# Telliskivi2014MainBoard.net
KiCad netlist of a schematic drawn in Altium Designer
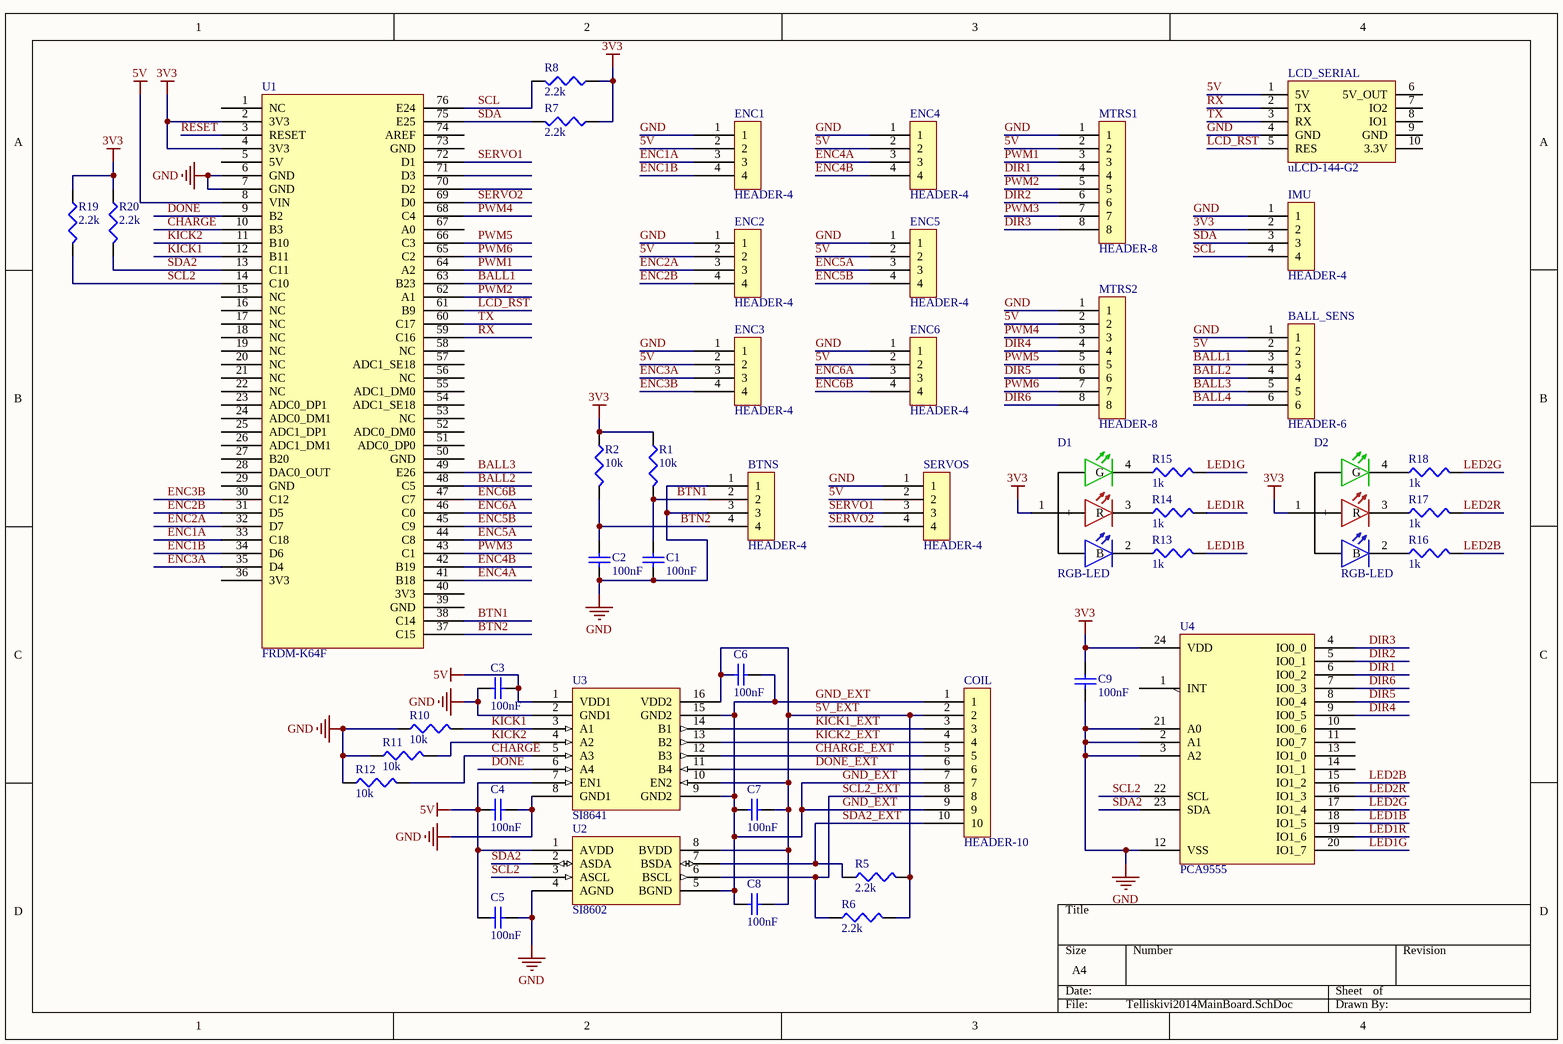
[diagram p0: Telliskivi2014MainBoard.SchDoc]

(export (version "E")
  (design (tool "Eeschema 10.0.6"))
  (components
    (comp (ref "BALL_SENS")
      (value "HEADER-6")
      (footprint "MICRO-MATCH-6")
      (libsource (lib "connectors") (part "HEADER-6"))
    )
    (comp (ref "BTNS")
      (value "HEADER-4")
      (footprint "MICRO-MATCH-4")
      (libsource (lib "connectors") (part "HEADER-4"))
    )
    (comp (ref "C1")
      (value "100nF")
      (footprint "1608[0603]")
      (description "Capacitor (Semiconductor SIM Model)")
      (fields (field (name "PUBLISHER") "Altium Limited"))
      (libsource (lib "Miscellaneous Devices") (part "Cap Semi"))
    )
    (comp (ref "C2")
      (value "100nF")
      (footprint "1608[0603]")
      (description "Capacitor (Semiconductor SIM Model)")
      (fields (field (name "PUBLISHER") "Altium Limited"))
      (libsource (lib "Miscellaneous Devices") (part "Cap Semi"))
    )
    (comp (ref "C3")
      (value "100nF")
      (footprint "1608[0603]")
      (description "Capacitor (Semiconductor SIM Model)")
      (fields (field (name "PUBLISHER") "Altium Limited"))
      (libsource (lib "Miscellaneous Devices") (part "Cap Semi"))
    )
    (comp (ref "C4")
      (value "100nF")
      (footprint "1608[0603]")
      (description "Capacitor (Semiconductor SIM Model)")
      (fields (field (name "PUBLISHER") "Altium Limited"))
      (libsource (lib "Miscellaneous Devices") (part "Cap Semi"))
    )
    (comp (ref "C5")
      (value "100nF")
      (footprint "1608[0603]")
      (description "Capacitor (Semiconductor SIM Model)")
      (fields (field (name "PUBLISHER") "Altium Limited"))
      (libsource (lib "Miscellaneous Devices") (part "Cap Semi"))
    )
    (comp (ref "C6")
      (value "100nF")
      (footprint "1608[0603]")
      (description "Capacitor (Semiconductor SIM Model)")
      (fields (field (name "PUBLISHER") "Altium Limited"))
      (libsource (lib "Miscellaneous Devices") (part "Cap Semi"))
    )
    (comp (ref "C7")
      (value "100nF")
      (footprint "1608[0603]")
      (description "Capacitor (Semiconductor SIM Model)")
      (fields (field (name "PUBLISHER") "Altium Limited"))
      (libsource (lib "Miscellaneous Devices") (part "Cap Semi"))
    )
    (comp (ref "C8")
      (value "100nF")
      (footprint "1608[0603]")
      (description "Capacitor (Semiconductor SIM Model)")
      (fields (field (name "PUBLISHER") "Altium Limited"))
      (libsource (lib "Miscellaneous Devices") (part "Cap Semi"))
    )
    (comp (ref "C9")
      (value "100nF")
      (footprint "1608[0603]")
      (description "Capacitor (Semiconductor SIM Model)")
      (fields (field (name "PUBLISHER") "Altium Limited"))
      (libsource (lib "Miscellaneous Devices") (part "Cap Semi"))
    )
    (comp (ref "COIL")
      (value "HEADER-10")
      (footprint "MICRO-MATCH-10")
      (libsource (lib "connectors") (part "HEADER-10"))
    )
    (comp (ref "D1") (value "RGB-LED") (footprint "RGB-LED") (libsource (lib "misc") (part "RGB-LED")))
    (comp (ref "D2") (value "RGB-LED") (footprint "RGB-LED") (libsource (lib "misc") (part "RGB-LED")))
    (comp (ref "ENC1")
      (value "HEADER-4")
      (footprint "MICRO-MATCH-4")
      (libsource (lib "connectors") (part "HEADER-4"))
    )
    (comp (ref "ENC2")
      (value "HEADER-4")
      (footprint "MICRO-MATCH-4")
      (libsource (lib "connectors") (part "HEADER-4"))
    )
    (comp (ref "ENC3")
      (value "HEADER-4")
      (footprint "MICRO-MATCH-4")
      (libsource (lib "connectors") (part "HEADER-4"))
    )
    (comp (ref "ENC4")
      (value "HEADER-4")
      (footprint "MICRO-MATCH-4")
      (libsource (lib "connectors") (part "HEADER-4"))
    )
    (comp (ref "ENC5")
      (value "HEADER-4")
      (footprint "MICRO-MATCH-4")
      (libsource (lib "connectors") (part "HEADER-4"))
    )
    (comp (ref "ENC6")
      (value "HEADER-4")
      (footprint "MICRO-MATCH-4")
      (libsource (lib "connectors") (part "HEADER-4"))
    )
    (comp (ref "IMU")
      (value "HEADER-4")
      (footprint "MICRO-MATCH-4")
      (libsource (lib "connectors") (part "HEADER-4"))
    )
    (comp (ref "LCD_SERIAL")
      (value "uLCD-144-G2")
      (footprint "uLCD-144-G2-NO-OVERLAY")
      (libsource (lib "misc") (part "uLCD-144-G2"))
    )
    (comp (ref "MTRS1")
      (value "HEADER-8")
      (footprint "MICRO-MATCH-8")
      (libsource (lib "connectors") (part "HEADER-8"))
    )
    (comp (ref "MTRS2")
      (value "HEADER-8")
      (footprint "MICRO-MATCH-8")
      (libsource (lib "connectors") (part "HEADER-8"))
    )
    (comp (ref "R1")
      (value "10k")
      (footprint "J1-0603")
      (description "Resistor")
      (fields (field (name "PUBLISHER") "Altium Limited"))
      (libsource (lib "Miscellaneous Devices") (part "Res3"))
    )
    (comp (ref "R2")
      (value "10k")
      (footprint "J1-0603")
      (description "Resistor")
      (fields (field (name "PUBLISHER") "Altium Limited"))
      (libsource (lib "Miscellaneous Devices") (part "Res3"))
    )
    (comp (ref "R5")
      (value "2.2k")
      (footprint "J1-0603")
      (description "Resistor")
      (fields (field (name "PUBLISHER") "Altium Limited"))
      (libsource (lib "Miscellaneous Devices") (part "Res3"))
    )
    (comp (ref "R6")
      (value "2.2k")
      (footprint "J1-0603")
      (description "Resistor")
      (fields (field (name "PUBLISHER") "Altium Limited"))
      (libsource (lib "Miscellaneous Devices") (part "Res3"))
    )
    (comp (ref "R7")
      (value "2.2k")
      (footprint "J1-0603")
      (description "Resistor")
      (fields (field (name "PUBLISHER") "Altium Limited"))
      (libsource (lib "Miscellaneous Devices") (part "Res3"))
    )
    (comp (ref "R8")
      (value "2.2k")
      (footprint "J1-0603")
      (description "Resistor")
      (fields (field (name "PUBLISHER") "Altium Limited"))
      (libsource (lib "Miscellaneous Devices") (part "Res3"))
    )
    (comp (ref "R10")
      (value "10k")
      (footprint "J1-0603")
      (description "Resistor")
      (fields (field (name "PUBLISHER") "Altium Limited"))
      (libsource (lib "Miscellaneous Devices") (part "Res3"))
    )
    (comp (ref "R11")
      (value "10k")
      (footprint "J1-0603")
      (description "Resistor")
      (fields (field (name "PUBLISHER") "Altium Limited"))
      (libsource (lib "Miscellaneous Devices") (part "Res3"))
    )
    (comp (ref "R12")
      (value "10k")
      (footprint "J1-0603")
      (description "Resistor")
      (fields (field (name "PUBLISHER") "Altium Limited"))
      (libsource (lib "Miscellaneous Devices") (part "Res3"))
    )
    (comp (ref "R13")
      (value "1k")
      (footprint "J1-0603")
      (description "Resistor")
      (fields (field (name "PUBLISHER") "Altium Limited"))
      (libsource (lib "Miscellaneous Devices") (part "Res3"))
    )
    (comp (ref "R14")
      (value "1k")
      (footprint "J1-0603")
      (description "Resistor")
      (fields (field (name "PUBLISHER") "Altium Limited"))
      (libsource (lib "Miscellaneous Devices") (part "Res3"))
    )
    (comp (ref "R15")
      (value "1k")
      (footprint "J1-0603")
      (description "Resistor")
      (fields (field (name "PUBLISHER") "Altium Limited"))
      (libsource (lib "Miscellaneous Devices") (part "Res3"))
    )
    (comp (ref "R16")
      (value "1k")
      (footprint "J1-0603")
      (description "Resistor")
      (fields (field (name "PUBLISHER") "Altium Limited"))
      (libsource (lib "Miscellaneous Devices") (part "Res3"))
    )
    (comp (ref "R17")
      (value "1k")
      (footprint "J1-0603")
      (description "Resistor")
      (fields (field (name "PUBLISHER") "Altium Limited"))
      (libsource (lib "Miscellaneous Devices") (part "Res3"))
    )
    (comp (ref "R18")
      (value "1k")
      (footprint "J1-0603")
      (description "Resistor")
      (fields (field (name "PUBLISHER") "Altium Limited"))
      (libsource (lib "Miscellaneous Devices") (part "Res3"))
    )
    (comp (ref "R19")
      (value "2.2k")
      (footprint "J1-0603")
      (description "Resistor")
      (fields (field (name "PUBLISHER") "Altium Limited"))
      (libsource (lib "Miscellaneous Devices") (part "Res3"))
    )
    (comp (ref "R20")
      (value "2.2k")
      (footprint "J1-0603")
      (description "Resistor")
      (fields (field (name "PUBLISHER") "Altium Limited"))
      (libsource (lib "Miscellaneous Devices") (part "Res3"))
    )
    (comp (ref "SERVOS")
      (value "HEADER-4")
      (footprint "MICRO-MATCH-4")
      (libsource (lib "connectors") (part "HEADER-4"))
    )
    (comp (ref "U1")
      (value "FRDM-K64F")
      (footprint "FRDM-K64F-SMT-NO-OVERLAY")
      (libsource (lib "mbed") (part "FRDM-K64F"))
    )
    (comp (ref "U2") (value "SI8602") (footprint "SOIC8") (libsource (lib "digital") (part "SI8602")))
    (comp (ref "U3") (value "SI8641") (footprint "SOIC16") (libsource (lib "digital") (part "SI8641")))
    (comp (ref "U4") (value "PCA9555") (footprint "TSSOP24") (libsource (lib "digital") (part "PCA9555")))
  )
  (nets
    (net (code "1") (name "/5V_EXT") (class "Default")
      (node (ref "C6") (pin "1") (pinfunction "1_1") (pintype "passive"))
      (node (ref "C7") (pin "2") (pinfunction "2_2") (pintype "passive"))
      (node (ref "C8") (pin "2") (pinfunction "2_2") (pintype "passive"))
      (node (ref "COIL") (pin "2") (pinfunction "2_2") (pintype "passive"))
      (node (ref "R5") (pin "2") (pinfunction "2_2") (pintype "passive"))
      (node (ref "R6") (pin "2") (pinfunction "2_2") (pintype "passive"))
      (node (ref "U2") (pin "8") (pinfunction "BVDD_8") (pintype "power_in"))
      (node (ref "U3") (pin "10") (pinfunction "EN2_10") (pintype "input"))
      (node (ref "U3") (pin "16") (pinfunction "VDD2_16") (pintype "power_in"))
    )
    (net (code "2") (name "/BALL1") (class "Default")
      (node (ref "BALL_SENS") (pin "3") (pinfunction "3_3") (pintype "passive"))
      (node (ref "U1") (pin "63") (pinfunction "B23_63") (pintype "passive"))
    )
    (net (code "3") (name "/BALL2") (class "Default")
      (node (ref "BALL_SENS") (pin "4") (pinfunction "4_4") (pintype "passive"))
      (node (ref "U1") (pin "48") (pinfunction "C5_48") (pintype "passive"))
    )
    (net (code "4") (name "/BALL3") (class "Default")
      (node (ref "BALL_SENS") (pin "5") (pinfunction "5_5") (pintype "passive"))
      (node (ref "U1") (pin "49") (pinfunction "E26_49") (pintype "passive"))
    )
    (net (code "5") (name "/BALL4") (class "Default")
      (node (ref "BALL_SENS") (pin "6") (pinfunction "6_6") (pintype "passive"))
    )
    (net (code "6") (name "/BTN1") (class "Default")
      (node (ref "BTNS") (pin "2") (pinfunction "2_2") (pintype "passive"))
      (node (ref "C1") (pin "2") (pinfunction "2_2") (pintype "passive"))
      (node (ref "R1") (pin "2") (pinfunction "2_2") (pintype "passive"))
      (node (ref "U1") (pin "38") (pinfunction "C14_38") (pintype "passive"))
    )
    (net (code "7") (name "/BTN2") (class "Default")
      (node (ref "BTNS") (pin "4") (pinfunction "4_4") (pintype "passive"))
      (node (ref "C2") (pin "2") (pinfunction "2_2") (pintype "passive"))
      (node (ref "R2") (pin "2") (pinfunction "2_2") (pintype "passive"))
      (node (ref "U1") (pin "37") (pinfunction "C15_37") (pintype "passive"))
    )
    (net (code "8") (name "/CHARGE") (class "Default")
      (node (ref "R12") (pin "2") (pinfunction "2_2") (pintype "passive"))
      (node (ref "U1") (pin "10") (pinfunction "B3_10") (pintype "passive"))
      (node (ref "U3") (pin "5") (pinfunction "A3_5") (pintype "input"))
    )
    (net (code "9") (name "/CHARGE_EXT") (class "Default")
      (node (ref "COIL") (pin "5") (pinfunction "5_5") (pintype "passive"))
      (node (ref "U3") (pin "12") (pinfunction "B3_12") (pintype "output"))
    )
    (net (code "10") (name "/DIR1") (class "Default")
      (node (ref "MTRS1") (pin "4") (pinfunction "4_4") (pintype "passive"))
      (node (ref "U4") (pin "6") (pinfunction "IO0_2_6") (pintype "passive"))
    )
    (net (code "11") (name "/DIR2") (class "Default")
      (node (ref "MTRS1") (pin "6") (pinfunction "6_6") (pintype "passive"))
      (node (ref "U4") (pin "5") (pinfunction "IO0_1_5") (pintype "passive"))
    )
    (net (code "12") (name "/DIR3") (class "Default")
      (node (ref "MTRS1") (pin "8") (pinfunction "8_8") (pintype "passive"))
      (node (ref "U4") (pin "4") (pinfunction "IO0_0_4") (pintype "passive"))
    )
    (net (code "13") (name "/DIR4") (class "Default")
      (node (ref "MTRS2") (pin "4") (pinfunction "4_4") (pintype "passive"))
      (node (ref "U4") (pin "9") (pinfunction "IO0_5_9") (pintype "passive"))
    )
    (net (code "14") (name "/DIR5") (class "Default")
      (node (ref "MTRS2") (pin "6") (pinfunction "6_6") (pintype "passive"))
      (node (ref "U4") (pin "8") (pinfunction "IO0_4_8") (pintype "passive"))
    )
    (net (code "15") (name "/DIR6") (class "Default")
      (node (ref "MTRS2") (pin "8") (pinfunction "8_8") (pintype "passive"))
      (node (ref "U4") (pin "7") (pinfunction "IO0_3_7") (pintype "passive"))
    )
    (net (code "16") (name "/DONE") (class "Default")
      (node (ref "U1") (pin "9") (pinfunction "B2_9") (pintype "passive"))
      (node (ref "U3") (pin "6") (pinfunction "A4_6") (pintype "input"))
    )
    (net (code "17") (name "/DONE_EXT") (class "Default")
      (node (ref "COIL") (pin "6") (pinfunction "6_6") (pintype "passive"))
      (node (ref "U3") (pin "11") (pinfunction "B4_11") (pintype "input"))
    )
    (net (code "18") (name "/ENC1A") (class "Default")
      (node (ref "ENC1") (pin "3") (pinfunction "3_3") (pintype "passive"))
      (node (ref "U1") (pin "33") (pinfunction "C18_33") (pintype "passive"))
    )
    (net (code "19") (name "/ENC1B") (class "Default")
      (node (ref "ENC1") (pin "4") (pinfunction "4_4") (pintype "passive"))
      (node (ref "U1") (pin "34") (pinfunction "D6_34") (pintype "passive"))
    )
    (net (code "20") (name "/ENC2A") (class "Default")
      (node (ref "ENC2") (pin "3") (pinfunction "3_3") (pintype "passive"))
      (node (ref "U1") (pin "32") (pinfunction "D7_32") (pintype "passive"))
    )
    (net (code "21") (name "/ENC2B") (class "Default")
      (node (ref "ENC2") (pin "4") (pinfunction "4_4") (pintype "passive"))
      (node (ref "U1") (pin "31") (pinfunction "D5_31") (pintype "passive"))
    )
    (net (code "22") (name "/ENC3A") (class "Default")
      (node (ref "ENC3") (pin "3") (pinfunction "3_3") (pintype "passive"))
      (node (ref "U1") (pin "35") (pinfunction "D4_35") (pintype "passive"))
    )
    (net (code "23") (name "/ENC3B") (class "Default")
      (node (ref "ENC3") (pin "4") (pinfunction "4_4") (pintype "passive"))
      (node (ref "U1") (pin "30") (pinfunction "C12_30") (pintype "passive"))
    )
    (net (code "24") (name "/ENC4A") (class "Default")
      (node (ref "ENC4") (pin "3") (pinfunction "3_3") (pintype "passive"))
      (node (ref "U1") (pin "41") (pinfunction "B18_41") (pintype "passive"))
    )
    (net (code "25") (name "/ENC4B") (class "Default")
      (node (ref "ENC4") (pin "4") (pinfunction "4_4") (pintype "passive"))
      (node (ref "U1") (pin "42") (pinfunction "B19_42") (pintype "passive"))
    )
    (net (code "26") (name "/ENC5A") (class "Default")
      (node (ref "ENC5") (pin "3") (pinfunction "3_3") (pintype "passive"))
      (node (ref "U1") (pin "44") (pinfunction "C8_44") (pintype "passive"))
    )
    (net (code "27") (name "/ENC5B") (class "Default")
      (node (ref "ENC5") (pin "4") (pinfunction "4_4") (pintype "passive"))
      (node (ref "U1") (pin "45") (pinfunction "C9_45") (pintype "passive"))
    )
    (net (code "28") (name "/ENC6A") (class "Default")
      (node (ref "ENC6") (pin "3") (pinfunction "3_3") (pintype "passive"))
      (node (ref "U1") (pin "46") (pinfunction "C0_46") (pintype "passive"))
    )
    (net (code "29") (name "/ENC6B") (class "Default")
      (node (ref "ENC6") (pin "4") (pinfunction "4_4") (pintype "passive"))
      (node (ref "U1") (pin "47") (pinfunction "C7_47") (pintype "passive"))
    )
    (net (code "30") (name "/GND_EXT") (class "Default")
      (node (ref "C6") (pin "2") (pinfunction "2_2") (pintype "passive"))
      (node (ref "C7") (pin "1") (pinfunction "1_1") (pintype "passive"))
      (node (ref "C8") (pin "1") (pinfunction "1_1") (pintype "passive"))
      (node (ref "COIL") (pin "1") (pinfunction "1_1") (pintype "passive"))
      (node (ref "COIL") (pin "7") (pinfunction "7_7") (pintype "passive"))
      (node (ref "COIL") (pin "9") (pinfunction "9_9") (pintype "passive"))
      (node (ref "U2") (pin "5") (pinfunction "BGND_5") (pintype "power_in"))
      (node (ref "U3") (pin "15") (pinfunction "GND2_15") (pintype "power_in"))
      (node (ref "U3") (pin "9") (pinfunction "GND2_9") (pintype "power_in"))
    )
    (net (code "31") (name "/KICK1") (class "Default")
      (node (ref "R10") (pin "2") (pinfunction "2_2") (pintype "passive"))
      (node (ref "U1") (pin "12") (pinfunction "B11_12") (pintype "passive"))
      (node (ref "U3") (pin "3") (pinfunction "A1_3") (pintype "input"))
    )
    (net (code "32") (name "/KICK1_EXT") (class "Default")
      (node (ref "COIL") (pin "3") (pinfunction "3_3") (pintype "passive"))
      (node (ref "U3") (pin "14") (pinfunction "B1_14") (pintype "output"))
    )
    (net (code "33") (name "/KICK2") (class "Default")
      (node (ref "R11") (pin "2") (pinfunction "2_2") (pintype "passive"))
      (node (ref "U1") (pin "11") (pinfunction "B10_11") (pintype "passive"))
      (node (ref "U3") (pin "4") (pinfunction "A2_4") (pintype "input"))
    )
    (net (code "34") (name "/KICK2_EXT") (class "Default")
      (node (ref "COIL") (pin "4") (pinfunction "4_4") (pintype "passive"))
      (node (ref "U3") (pin "13") (pinfunction "B2_13") (pintype "output"))
    )
    (net (code "35") (name "/LCD_RST") (class "Default")
      (node (ref "LCD_SERIAL") (pin "5") (pinfunction "RES_5") (pintype "passive"))
      (node (ref "U1") (pin "61") (pinfunction "B9_61") (pintype "passive"))
    )
    (net (code "36") (name "/LED1B") (class "Default")
      (node (ref "R13") (pin "2") (pinfunction "2_2") (pintype "passive"))
      (node (ref "U4") (pin "18") (pinfunction "IO1_5_18") (pintype "passive"))
    )
    (net (code "37") (name "/LED1G") (class "Default")
      (node (ref "R15") (pin "2") (pinfunction "2_2") (pintype "passive"))
      (node (ref "U4") (pin "20") (pinfunction "IO1_7_20") (pintype "passive"))
    )
    (net (code "38") (name "/LED1R") (class "Default")
      (node (ref "R14") (pin "2") (pinfunction "2_2") (pintype "passive"))
      (node (ref "U4") (pin "19") (pinfunction "IO1_6_19") (pintype "passive"))
    )
    (net (code "39") (name "/LED2B") (class "Default")
      (node (ref "R16") (pin "2") (pinfunction "2_2") (pintype "passive"))
      (node (ref "U4") (pin "15") (pinfunction "IO1_2_15") (pintype "passive"))
    )
    (net (code "40") (name "/LED2G") (class "Default")
      (node (ref "R18") (pin "2") (pinfunction "2_2") (pintype "passive"))
      (node (ref "U4") (pin "17") (pinfunction "IO1_4_17") (pintype "passive"))
    )
    (net (code "41") (name "/LED2R") (class "Default")
      (node (ref "R17") (pin "2") (pinfunction "2_2") (pintype "passive"))
      (node (ref "U4") (pin "16") (pinfunction "IO1_3_16") (pintype "passive"))
    )
    (net (code "42") (name "/PWM1") (class "Default")
      (node (ref "MTRS1") (pin "3") (pinfunction "3_3") (pintype "passive"))
      (node (ref "U1") (pin "64") (pinfunction "A2_64") (pintype "passive"))
    )
    (net (code "43") (name "/PWM2") (class "Default")
      (node (ref "MTRS1") (pin "5") (pinfunction "5_5") (pintype "passive"))
      (node (ref "U1") (pin "62") (pinfunction "A1_62") (pintype "passive"))
    )
    (net (code "44") (name "/PWM3") (class "Default")
      (node (ref "MTRS1") (pin "7") (pinfunction "7_7") (pintype "passive"))
      (node (ref "U1") (pin "43") (pinfunction "C1_43") (pintype "passive"))
    )
    (net (code "45") (name "/PWM4") (class "Default")
      (node (ref "MTRS2") (pin "3") (pinfunction "3_3") (pintype "passive"))
      (node (ref "U1") (pin "68") (pinfunction "C4_68") (pintype "passive"))
    )
    (net (code "46") (name "/PWM5") (class "Default")
      (node (ref "MTRS2") (pin "5") (pinfunction "5_5") (pintype "passive"))
      (node (ref "U1") (pin "66") (pinfunction "C3_66") (pintype "passive"))
    )
    (net (code "47") (name "/PWM6") (class "Default")
      (node (ref "MTRS2") (pin "7") (pinfunction "7_7") (pintype "passive"))
      (node (ref "U1") (pin "65") (pinfunction "C2_65") (pintype "passive"))
    )
    (net (code "48") (name "/RESET") (class "Default")
      (node (ref "U1") (pin "3") (pinfunction "RESET_3") (pintype "passive"))
    )
    (net (code "49") (name "/RX") (class "Default")
      (node (ref "LCD_SERIAL") (pin "2") (pinfunction "TX_2") (pintype "passive"))
      (node (ref "U1") (pin "59") (pinfunction "C16_59") (pintype "passive"))
    )
    (net (code "50") (name "/SCL") (class "Default")
      (node (ref "IMU") (pin "4") (pinfunction "4_4") (pintype "passive"))
      (node (ref "R8") (pin "2") (pinfunction "2_2") (pintype "passive"))
      (node (ref "U1") (pin "76") (pinfunction "E24_76") (pintype "passive"))
    )
    (net (code "51") (name "/SCL2") (class "Default")
      (node (ref "R19") (pin "2") (pinfunction "2_2") (pintype "passive"))
      (node (ref "U1") (pin "14") (pinfunction "C10_14") (pintype "passive"))
      (node (ref "U2") (pin "3") (pinfunction "ASCL_3") (pintype "input"))
      (node (ref "U4") (pin "22") (pinfunction "SCL_22") (pintype "passive"))
    )
    (net (code "52") (name "/SCL2_EXT") (class "Default")
      (node (ref "COIL") (pin "8") (pinfunction "8_8") (pintype "passive"))
      (node (ref "R6") (pin "1") (pinfunction "1_1") (pintype "passive"))
      (node (ref "U2") (pin "6") (pinfunction "BSCL_6") (pintype "output"))
    )
    (net (code "53") (name "/SDA") (class "Default")
      (node (ref "IMU") (pin "3") (pinfunction "3_3") (pintype "passive"))
      (node (ref "R7") (pin "2") (pinfunction "2_2") (pintype "passive"))
      (node (ref "U1") (pin "75") (pinfunction "E25_75") (pintype "passive"))
    )
    (net (code "54") (name "/SDA2") (class "Default")
      (node (ref "R20") (pin "2") (pinfunction "2_2") (pintype "passive"))
      (node (ref "U1") (pin "13") (pinfunction "C11_13") (pintype "passive"))
      (node (ref "U2") (pin "2") (pinfunction "ASDA_2") (pintype "bidirectional"))
      (node (ref "U4") (pin "23") (pinfunction "SDA_23") (pintype "passive"))
    )
    (net (code "55") (name "/SDA2_EXT") (class "Default")
      (node (ref "COIL") (pin "10") (pinfunction "10_10") (pintype "passive"))
      (node (ref "R5") (pin "1") (pinfunction "1_1") (pintype "passive"))
      (node (ref "U2") (pin "7") (pinfunction "BSDA_7") (pintype "bidirectional"))
    )
    (net (code "56") (name "/SERVO1") (class "Default")
      (node (ref "SERVOS") (pin "3") (pinfunction "3_3") (pintype "passive"))
      (node (ref "U1") (pin "72") (pinfunction "D1_72") (pintype "passive"))
    )
    (net (code "57") (name "/SERVO2") (class "Default")
      (node (ref "SERVOS") (pin "4") (pinfunction "4_4") (pintype "passive"))
      (node (ref "U1") (pin "69") (pinfunction "D0_69") (pintype "passive"))
    )
    (net (code "58") (name "/TX") (class "Default")
      (node (ref "LCD_SERIAL") (pin "3") (pinfunction "RX_3") (pintype "passive"))
      (node (ref "U1") (pin "60") (pinfunction "C17_60") (pintype "passive"))
    )
    (net (code "59") (name "3V3") (class "Default")
      (node (ref "C9") (pin "2") (pinfunction "2_2") (pintype "passive"))
      (node (ref "D1") (pin "1") (pinfunction "+_1") (pintype "passive"))
      (node (ref "D2") (pin "1") (pinfunction "+_1") (pintype "passive"))
      (node (ref "IMU") (pin "2") (pinfunction "2_2") (pintype "passive"))
      (node (ref "R1") (pin "1") (pinfunction "1_1") (pintype "passive"))
      (node (ref "R19") (pin "1") (pinfunction "1_1") (pintype "passive"))
      (node (ref "R2") (pin "1") (pinfunction "1_1") (pintype "passive"))
      (node (ref "R20") (pin "1") (pinfunction "1_1") (pintype "passive"))
      (node (ref "R7") (pin "1") (pinfunction "1_1") (pintype "passive"))
      (node (ref "R8") (pin "1") (pinfunction "1_1") (pintype "passive"))
      (node (ref "U1") (pin "2") (pinfunction "3V3_2") (pintype "passive"))
      (node (ref "U1") (pin "4") (pinfunction "3V3_4") (pintype "passive"))
      (node (ref "U4") (pin "24") (pinfunction "VDD_24") (pintype "passive"))
    )
    (net (code "60") (name "5V") (class "Default")
      (node (ref "BALL_SENS") (pin "2") (pinfunction "2_2") (pintype "passive"))
      (node (ref "C3") (pin "2") (pinfunction "2_2") (pintype "passive"))
      (node (ref "C4") (pin "1") (pinfunction "1_1") (pintype "passive"))
      (node (ref "C5") (pin "1") (pinfunction "1_1") (pintype "passive"))
      (node (ref "ENC1") (pin "2") (pinfunction "2_2") (pintype "passive"))
      (node (ref "ENC2") (pin "2") (pinfunction "2_2") (pintype "passive"))
      (node (ref "ENC3") (pin "2") (pinfunction "2_2") (pintype "passive"))
      (node (ref "ENC4") (pin "2") (pinfunction "2_2") (pintype "passive"))
      (node (ref "ENC5") (pin "2") (pinfunction "2_2") (pintype "passive"))
      (node (ref "ENC6") (pin "2") (pinfunction "2_2") (pintype "passive"))
      (node (ref "LCD_SERIAL") (pin "1") (pinfunction "5V_1") (pintype "passive"))
      (node (ref "MTRS1") (pin "2") (pinfunction "2_2") (pintype "passive"))
      (node (ref "MTRS2") (pin "2") (pinfunction "2_2") (pintype "passive"))
      (node (ref "SERVOS") (pin "2") (pinfunction "2_2") (pintype "passive"))
      (node (ref "U1") (pin "8") (pinfunction "VIN_8") (pintype "passive"))
      (node (ref "U2") (pin "1") (pinfunction "AVDD_1") (pintype "power_in"))
      (node (ref "U3") (pin "1") (pinfunction "VDD1_1") (pintype "power_in"))
      (node (ref "U3") (pin "7") (pinfunction "EN1_7") (pintype "input"))
    )
    (net (code "61") (name "GND") (class "Default")
      (node (ref "BALL_SENS") (pin "1") (pinfunction "1_1") (pintype "passive"))
      (node (ref "BTNS") (pin "1") (pinfunction "1_1") (pintype "passive"))
      (node (ref "BTNS") (pin "3") (pinfunction "3_3") (pintype "passive"))
      (node (ref "C1") (pin "1") (pinfunction "1_1") (pintype "passive"))
      (node (ref "C2") (pin "1") (pinfunction "1_1") (pintype "passive"))
      (node (ref "C3") (pin "1") (pinfunction "1_1") (pintype "passive"))
      (node (ref "C4") (pin "2") (pinfunction "2_2") (pintype "passive"))
      (node (ref "C5") (pin "2") (pinfunction "2_2") (pintype "passive"))
      (node (ref "C9") (pin "1") (pinfunction "1_1") (pintype "passive"))
      (node (ref "ENC1") (pin "1") (pinfunction "1_1") (pintype "passive"))
      (node (ref "ENC2") (pin "1") (pinfunction "1_1") (pintype "passive"))
      (node (ref "ENC3") (pin "1") (pinfunction "1_1") (pintype "passive"))
      (node (ref "ENC4") (pin "1") (pinfunction "1_1") (pintype "passive"))
      (node (ref "ENC5") (pin "1") (pinfunction "1_1") (pintype "passive"))
      (node (ref "ENC6") (pin "1") (pinfunction "1_1") (pintype "passive"))
      (node (ref "IMU") (pin "1") (pinfunction "1_1") (pintype "passive"))
      (node (ref "LCD_SERIAL") (pin "4") (pinfunction "GND_4") (pintype "passive"))
      (node (ref "MTRS1") (pin "1") (pinfunction "1_1") (pintype "passive"))
      (node (ref "MTRS2") (pin "1") (pinfunction "1_1") (pintype "passive"))
      (node (ref "R10") (pin "1") (pinfunction "1_1") (pintype "passive"))
      (node (ref "R11") (pin "1") (pinfunction "1_1") (pintype "passive"))
      (node (ref "R12") (pin "1") (pinfunction "1_1") (pintype "passive"))
      (node (ref "SERVOS") (pin "1") (pinfunction "1_1") (pintype "passive"))
      (node (ref "U1") (pin "6") (pinfunction "GND_6") (pintype "passive"))
      (node (ref "U1") (pin "7") (pinfunction "GND_7") (pintype "passive"))
      (node (ref "U2") (pin "4") (pinfunction "AGND_4") (pintype "power_in"))
      (node (ref "U3") (pin "2") (pinfunction "GND1_2") (pintype "power_in"))
      (node (ref "U3") (pin "8") (pinfunction "GND1_8") (pintype "power_in"))
      (node (ref "U4") (pin "12") (pinfunction "VSS_12") (pintype "passive"))
      (node (ref "U4") (pin "2") (pinfunction "A1_2") (pintype "passive"))
      (node (ref "U4") (pin "21") (pinfunction "A0_21") (pintype "passive"))
      (node (ref "U4") (pin "3") (pinfunction "A2_3") (pintype "passive"))
    )
    (net (code "62") (name "Net-(D1-B)") (class "Default")
      (node (ref "D1") (pin "2") (pinfunction "B_2") (pintype "passive"))
      (node (ref "R13") (pin "1") (pinfunction "1_1") (pintype "passive"))
    )
    (net (code "63") (name "Net-(D1-G)") (class "Default")
      (node (ref "D1") (pin "4") (pinfunction "G_4") (pintype "passive"))
      (node (ref "R15") (pin "1") (pinfunction "1_1") (pintype "passive"))
    )
    (net (code "64") (name "Net-(D1-R)") (class "Default")
      (node (ref "D1") (pin "3") (pinfunction "R_3") (pintype "passive"))
      (node (ref "R14") (pin "1") (pinfunction "1_1") (pintype "passive"))
    )
    (net (code "65") (name "Net-(D2-B)") (class "Default")
      (node (ref "D2") (pin "2") (pinfunction "B_2") (pintype "passive"))
      (node (ref "R16") (pin "1") (pinfunction "1_1") (pintype "passive"))
    )
    (net (code "66") (name "Net-(D2-G)") (class "Default")
      (node (ref "D2") (pin "4") (pinfunction "G_4") (pintype "passive"))
      (node (ref "R18") (pin "1") (pinfunction "1_1") (pintype "passive"))
    )
    (net (code "67") (name "Net-(D2-R)") (class "Default")
      (node (ref "D2") (pin "3") (pinfunction "R_3") (pintype "passive"))
      (node (ref "R17") (pin "1") (pinfunction "1_1") (pintype "passive"))
    )
    (net (code "68") (name "unconnected-(LCD_SERIAL-3.3V-Pad10)") (class "Default")
      (node (ref "LCD_SERIAL") (pin "10") (pinfunction "3.3V_10") (pintype "passive"))
    )
    (net (code "69") (name "unconnected-(LCD_SERIAL-5V_OUT-Pad6)") (class "Default")
      (node (ref "LCD_SERIAL") (pin "6") (pinfunction "5V_OUT_6") (pintype "passive"))
    )
    (net (code "70") (name "unconnected-(LCD_SERIAL-GND-Pad9)") (class "Default")
      (node (ref "LCD_SERIAL") (pin "9") (pinfunction "GND_9") (pintype "passive"))
    )
    (net (code "71") (name "unconnected-(LCD_SERIAL-IO1-Pad8)") (class "Default")
      (node (ref "LCD_SERIAL") (pin "8") (pinfunction "IO1_8") (pintype "passive"))
    )
    (net (code "72") (name "unconnected-(LCD_SERIAL-IO2-Pad7)") (class "Default")
      (node (ref "LCD_SERIAL") (pin "7") (pinfunction "IO2_7") (pintype "passive"))
    )
    (net (code "73") (name "unconnected-(U1-3V3-Pad36)") (class "Default")
      (node (ref "U1") (pin "36") (pinfunction "3V3_36") (pintype "passive"))
    )
    (net (code "74") (name "unconnected-(U1-3V3-Pad40)") (class "Default")
      (node (ref "U1") (pin "40") (pinfunction "3V3_40") (pintype "passive"))
    )
    (net (code "75") (name "unconnected-(U1-5V-Pad5)") (class "Default")
      (node (ref "U1") (pin "5") (pinfunction "5V_5") (pintype "passive"))
    )
    (net (code "76") (name "unconnected-(U1-A0-Pad67)") (class "Default")
      (node (ref "U1") (pin "67") (pinfunction "A0_67") (pintype "passive"))
    )
    (net (code "77") (name "unconnected-(U1-ADC0_DM0-Pad52)") (class "Default")
      (node (ref "U1") (pin "52") (pinfunction "ADC0_DM0_52") (pintype "passive"))
    )
    (net (code "78") (name "unconnected-(U1-ADC0_DM1-Pad24)") (class "Default")
      (node (ref "U1") (pin "24") (pinfunction "ADC0_DM1_24") (pintype "passive"))
    )
    (net (code "79") (name "unconnected-(U1-ADC0_DP0-Pad51)") (class "Default")
      (node (ref "U1") (pin "51") (pinfunction "ADC0_DP0_51") (pintype "passive"))
    )
    (net (code "80") (name "unconnected-(U1-ADC0_DP1-Pad23)") (class "Default")
      (node (ref "U1") (pin "23") (pinfunction "ADC0_DP1_23") (pintype "passive"))
    )
    (net (code "81") (name "unconnected-(U1-ADC1_DM0-Pad55)") (class "Default")
      (node (ref "U1") (pin "55") (pinfunction "ADC1_DM0_55") (pintype "passive"))
    )
    (net (code "82") (name "unconnected-(U1-ADC1_DM1-Pad26)") (class "Default")
      (node (ref "U1") (pin "26") (pinfunction "ADC1_DM1_26") (pintype "passive"))
    )
    (net (code "83") (name "unconnected-(U1-ADC1_DP1-Pad25)") (class "Default")
      (node (ref "U1") (pin "25") (pinfunction "ADC1_DP1_25") (pintype "passive"))
    )
    (net (code "84") (name "unconnected-(U1-ADC1_SE18-Pad54)") (class "Default")
      (node (ref "U1") (pin "54") (pinfunction "ADC1_SE18_54") (pintype "passive"))
    )
    (net (code "85") (name "unconnected-(U1-ADC1_SE18-Pad57)") (class "Default")
      (node (ref "U1") (pin "57") (pinfunction "ADC1_SE18_57") (pintype "passive"))
    )
    (net (code "86") (name "unconnected-(U1-AREF-Pad74)") (class "Default")
      (node (ref "U1") (pin "74") (pinfunction "AREF_74") (pintype "passive"))
    )
    (net (code "87") (name "unconnected-(U1-B20-Pad27)") (class "Default")
      (node (ref "U1") (pin "27") (pinfunction "B20_27") (pintype "passive"))
    )
    (net (code "88") (name "unconnected-(U1-D2-Pad70)") (class "Default")
      (node (ref "U1") (pin "70") (pinfunction "D2_70") (pintype "passive"))
    )
    (net (code "89") (name "unconnected-(U1-D3-Pad71)") (class "Default")
      (node (ref "U1") (pin "71") (pinfunction "D3_71") (pintype "passive"))
    )
    (net (code "90") (name "unconnected-(U1-DAC0_OUT-Pad28)") (class "Default")
      (node (ref "U1") (pin "28") (pinfunction "DAC0_OUT_28") (pintype "passive"))
    )
    (net (code "91") (name "unconnected-(U1-GND-Pad29)") (class "Default")
      (node (ref "U1") (pin "29") (pinfunction "GND_29") (pintype "passive"))
    )
    (net (code "92") (name "unconnected-(U1-GND-Pad39)") (class "Default")
      (node (ref "U1") (pin "39") (pinfunction "GND_39") (pintype "passive"))
    )
    (net (code "93") (name "unconnected-(U1-GND-Pad50)") (class "Default")
      (node (ref "U1") (pin "50") (pinfunction "GND_50") (pintype "passive"))
    )
    (net (code "94") (name "unconnected-(U1-GND-Pad73)") (class "Default")
      (node (ref "U1") (pin "73") (pinfunction "GND_73") (pintype "passive"))
    )
    (net (code "95") (name "unconnected-(U1-NC-Pad1)") (class "Default")
      (node (ref "U1") (pin "1") (pinfunction "NC_1") (pintype "passive"))
    )
    (net (code "96") (name "unconnected-(U1-NC-Pad15)") (class "Default")
      (node (ref "U1") (pin "15") (pinfunction "NC_15") (pintype "passive"))
    )
    (net (code "97") (name "unconnected-(U1-NC-Pad16)") (class "Default")
      (node (ref "U1") (pin "16") (pinfunction "NC_16") (pintype "passive"))
    )
    (net (code "98") (name "unconnected-(U1-NC-Pad17)") (class "Default")
      (node (ref "U1") (pin "17") (pinfunction "NC_17") (pintype "passive"))
    )
    (net (code "99") (name "unconnected-(U1-NC-Pad18)") (class "Default")
      (node (ref "U1") (pin "18") (pinfunction "NC_18") (pintype "passive"))
    )
    (net (code "100") (name "unconnected-(U1-NC-Pad19)") (class "Default")
      (node (ref "U1") (pin "19") (pinfunction "NC_19") (pintype "passive"))
    )
    (net (code "101") (name "unconnected-(U1-NC-Pad20)") (class "Default")
      (node (ref "U1") (pin "20") (pinfunction "NC_20") (pintype "passive"))
    )
    (net (code "102") (name "unconnected-(U1-NC-Pad21)") (class "Default")
      (node (ref "U1") (pin "21") (pinfunction "NC_21") (pintype "passive"))
    )
    (net (code "103") (name "unconnected-(U1-NC-Pad22)") (class "Default")
      (node (ref "U1") (pin "22") (pinfunction "NC_22") (pintype "passive"))
    )
    (net (code "104") (name "unconnected-(U1-NC-Pad53)") (class "Default")
      (node (ref "U1") (pin "53") (pinfunction "NC_53") (pintype "passive"))
    )
    (net (code "105") (name "unconnected-(U1-NC-Pad56)") (class "Default")
      (node (ref "U1") (pin "56") (pinfunction "NC_56") (pintype "passive"))
    )
    (net (code "106") (name "unconnected-(U1-NC-Pad58)") (class "Default")
      (node (ref "U1") (pin "58") (pinfunction "NC_58") (pintype "passive"))
    )
    (net (code "107") (name "unconnected-(U4-INT-Pad1)") (class "Default")
      (node (ref "U4") (pin "1") (pinfunction "INT_1") (pintype "open_collector"))
    )
    (net (code "108") (name "unconnected-(U4-IO0_6-Pad10)") (class "Default")
      (node (ref "U4") (pin "10") (pinfunction "IO0_6_10") (pintype "passive"))
    )
    (net (code "109") (name "unconnected-(U4-IO0_7-Pad11)") (class "Default")
      (node (ref "U4") (pin "11") (pinfunction "IO0_7_11") (pintype "passive"))
    )
    (net (code "110") (name "unconnected-(U4-IO1_0-Pad13)") (class "Default")
      (node (ref "U4") (pin "13") (pinfunction "IO1_0_13") (pintype "passive"))
    )
    (net (code "111") (name "unconnected-(U4-IO1_1-Pad14)") (class "Default")
      (node (ref "U4") (pin "14") (pinfunction "IO1_1_14") (pintype "passive"))
    )
  )
)
